# C283x_DSP.net
KiCad netlist of a schematic drawn in Altium Designer
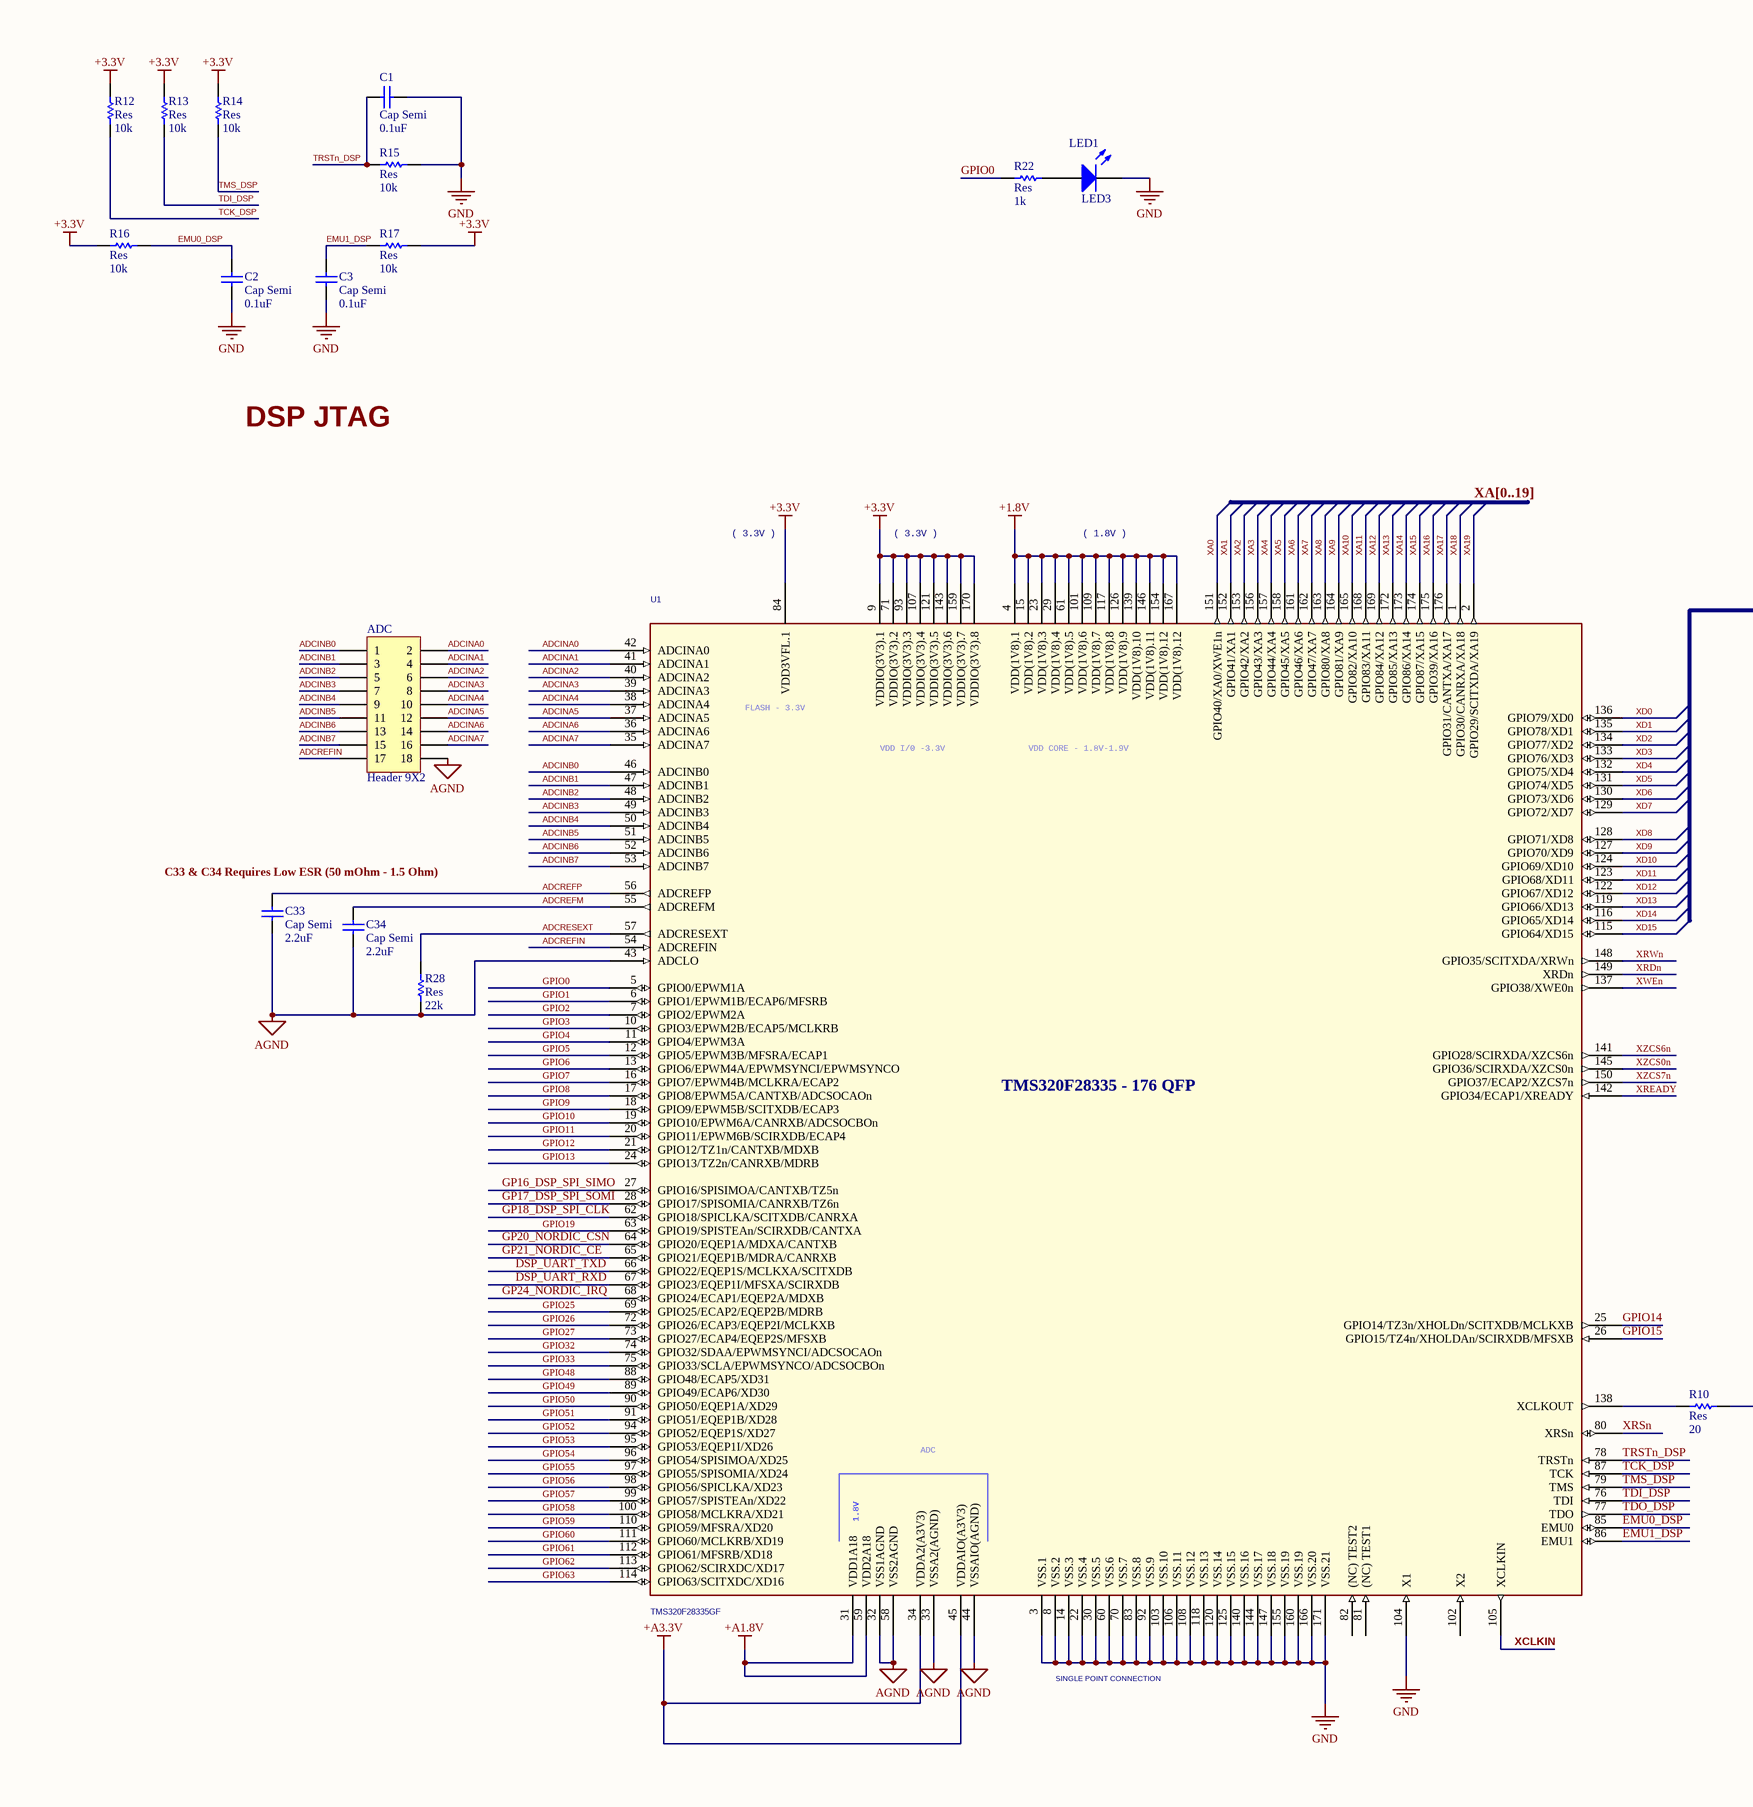
[diagram p0: C283x_DSP.SchDoc, left]
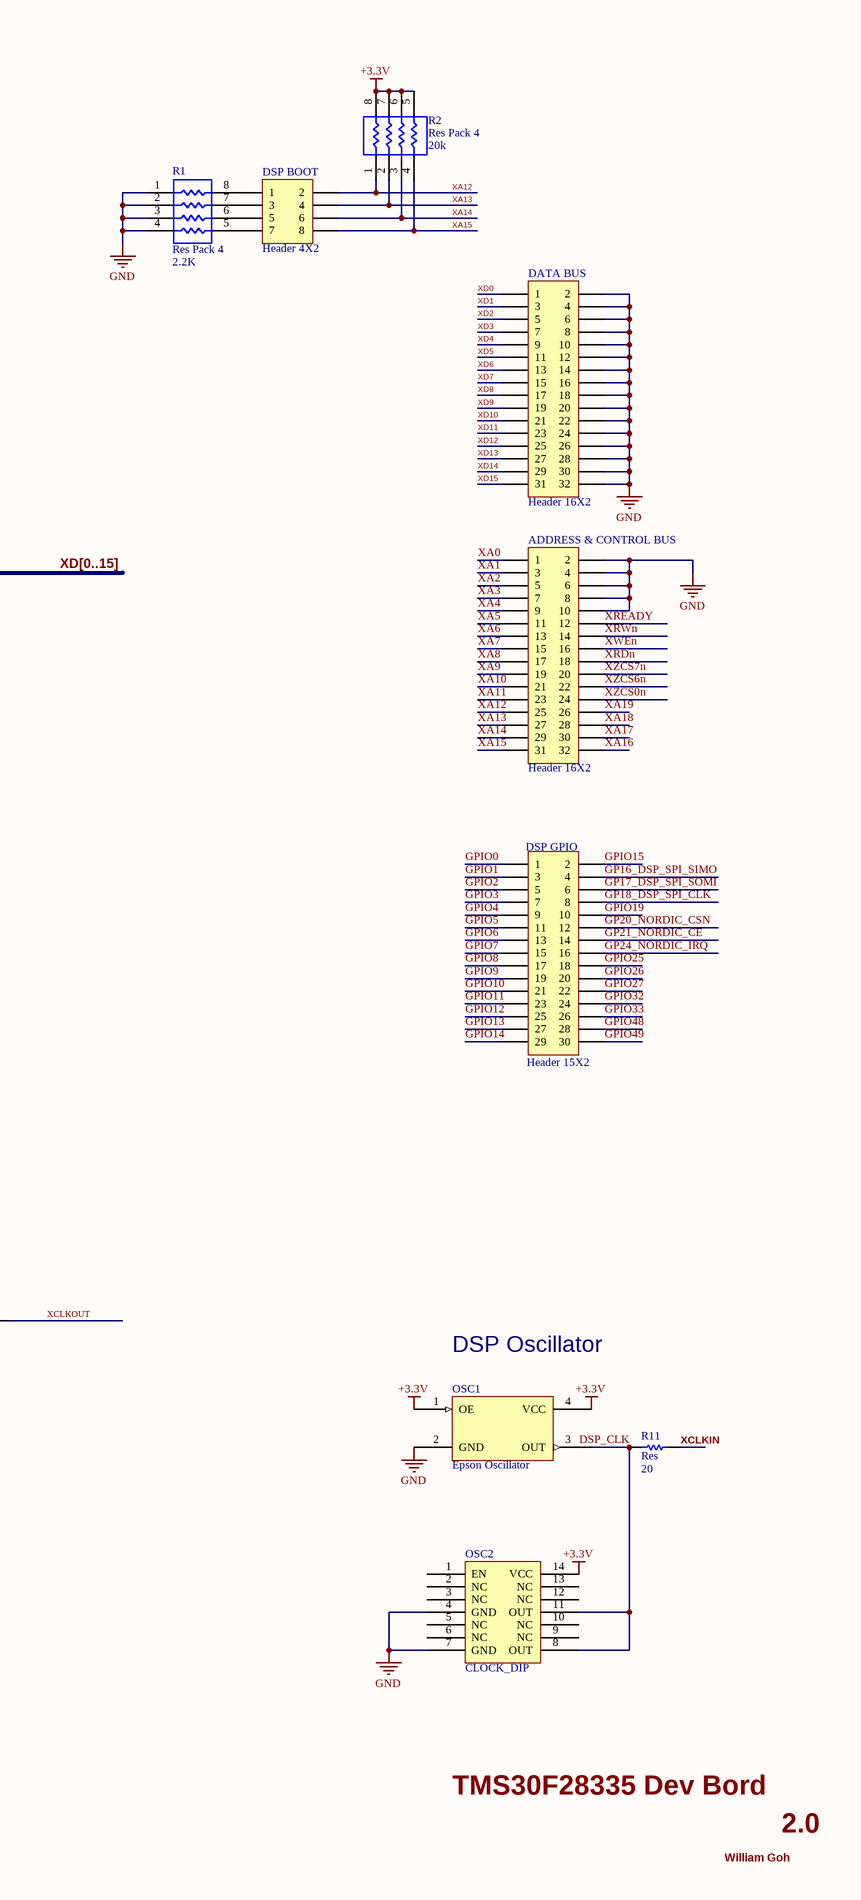
[diagram p1: C283x_DSP.SchDoc, right]

(export (version "E")
  (design (tool "Eeschema 10.0.6"))
  (components
    (comp (ref "ADC")
      (value "Header 9X2")
      (footprint "HDR2X9")
      (description "Header, 9-Pin, Dual row")
      (fields (field (name "PUBLISHER") "Altium Limited"))
      (libsource (lib "Miscellaneous Connectors") (part "Header 9X2"))
    )
    (comp (ref "ADDRESS & CONTROL BUS")
      (value "Header 16X2")
      (footprint "HDR2X16")
      (description "Header, 16-Pin, Dual row")
      (fields (field (name "PUBLISHER") "Altium Limited"))
      (libsource (lib "Miscellaneous Connectors") (part "Header 16X2"))
    )
    (comp (ref "C1")
      (value "Cap Semi")
      (footprint "0805")
      (description "Capacitor (Semiconductor SIM Model)")
      (fields (field (name "ALTIUM_VALUE") "0.1uF") (field (name "PUBLISHER") "Altium Limited"))
      (libsource (lib "Miscellaneous Devices") (part "Cap Semi"))
    )
    (comp (ref "C2")
      (value "Cap Semi")
      (footprint "0805")
      (description "Capacitor (Semiconductor SIM Model)")
      (fields (field (name "ALTIUM_VALUE") "0.1uF") (field (name "PUBLISHER") "Altium Limited"))
      (libsource (lib "Miscellaneous Devices") (part "Cap Semi"))
    )
    (comp (ref "C3")
      (value "Cap Semi")
      (footprint "0805")
      (description "Capacitor (Semiconductor SIM Model)")
      (fields (field (name "ALTIUM_VALUE") "0.1uF") (field (name "PUBLISHER") "Altium Limited"))
      (libsource (lib "Miscellaneous Devices") (part "Cap Semi"))
    )
    (comp (ref "C33")
      (value "Cap Semi")
      (footprint "0805")
      (description "Capacitor (Semiconductor SIM Model)")
      (fields (field (name "ALTIUM_VALUE") "2.2uF") (field (name "PUBLISHER") "Altium Limited"))
      (libsource (lib "Miscellaneous Devices") (part "Cap Semi"))
    )
    (comp (ref "C34")
      (value "Cap Semi")
      (footprint "0805")
      (description "Capacitor (Semiconductor SIM Model)")
      (fields (field (name "ALTIUM_VALUE") "2.2uF") (field (name "PUBLISHER") "Altium Limited"))
      (libsource (lib "Miscellaneous Devices") (part "Cap Semi"))
    )
    (comp (ref "DATA BUS")
      (value "Header 16X2")
      (footprint "HDR2X16")
      (description "Header, 16-Pin, Dual row")
      (fields (field (name "PUBLISHER") "Altium Limited"))
      (libsource (lib "Miscellaneous Connectors") (part "Header 16X2"))
    )
    (comp (ref "DSP BOOT")
      (value "Header 4X2")
      (footprint "HDR2X4")
      (description "Header, 4-Pin, Dual row")
      (fields (field (name "PUBLISHER") "Altium Limited"))
      (libsource (lib "Miscellaneous Connectors") (part "Header 4X2"))
    )
    (comp (ref "DSP GPIO")
      (value "Header 15X2")
      (footprint "HDR2X15")
      (description "Header, 15-Pin, Dual row")
      (fields (field (name "PUBLISHER") "Altium Limited"))
      (libsource (lib "Miscellaneous Connectors") (part "Header 15X2"))
    )
    (comp (ref "LED1")
      (value "LED3")
      (footprint "0805")
      (description "Typical BLUE SiC LED")
      (fields (field (name "PUBLISHER") "Altium Limited"))
      (libsource (lib "Miscellaneous Devices") (part "LED3"))
    )
    (comp (ref "OSC1")
      (value "Epson Oscillator")
      (footprint "Oscillator")
      (description "15Mhz Epson Clock")
      (libsource (lib "F28335_DSC_Breakout") (part "Oscillator"))
    )
    (comp (ref "OSC2") (value "CLOCK_DIP") (footprint "DIP-14") (libsource (lib "*") (part "CLOCK_DIP")))
    (comp (ref "R1")
      (value "Res Pack 4")
      (footprint "SO-8")
      (description "4 Isolated Resistor Network")
      (fields (field (name "ALTIUM_VALUE") "2.2K") (field (name "PUBLISHER") "Altium Limited"))
      (libsource (lib "F28335_DSC_Breakout") (part "Res Pack 4"))
    )
    (comp (ref "R2")
      (value "Res Pack 4")
      (footprint "SO-8")
      (description "4 Isolated Resistor Network")
      (fields (field (name "ALTIUM_VALUE") "20k") (field (name "PUBLISHER") "Altium Limited"))
      (libsource (lib "F28335_DSC_Breakout") (part "Res Pack 4"))
    )
    (comp (ref "R10")
      (value "Res")
      (footprint "0805")
      (description "Semiconductor Resistor")
      (fields (field (name "ALTIUM_VALUE") "20") (field (name "PUBLISHER") "Altium Limited"))
      (libsource (lib "F28335_DSC_Breakout") (part "Res Semi"))
    )
    (comp (ref "R11")
      (value "Res")
      (footprint "0805")
      (description "Semiconductor Resistor")
      (fields (field (name "ALTIUM_VALUE") "20") (field (name "PUBLISHER") "Altium Limited"))
      (libsource (lib "F28335_DSC_Breakout") (part "Res Semi"))
    )
    (comp (ref "R12")
      (value "Res")
      (footprint "0805")
      (description "Semiconductor Resistor")
      (fields (field (name "ALTIUM_VALUE") "10k") (field (name "PUBLISHER") "Altium Limited"))
      (libsource (lib "F28335_DSC_Breakout") (part "Res Semi"))
    )
    (comp (ref "R13")
      (value "Res")
      (footprint "0805")
      (description "Semiconductor Resistor")
      (fields (field (name "ALTIUM_VALUE") "10k") (field (name "PUBLISHER") "Altium Limited"))
      (libsource (lib "F28335_DSC_Breakout") (part "Res Semi"))
    )
    (comp (ref "R14")
      (value "Res")
      (footprint "0805")
      (description "Semiconductor Resistor")
      (fields (field (name "ALTIUM_VALUE") "10k") (field (name "PUBLISHER") "Altium Limited"))
      (libsource (lib "F28335_DSC_Breakout") (part "Res Semi"))
    )
    (comp (ref "R15")
      (value "Res")
      (footprint "0805")
      (description "Semiconductor Resistor")
      (fields (field (name "ALTIUM_VALUE") "10k") (field (name "PUBLISHER") "Altium Limited"))
      (libsource (lib "F28335_DSC_Breakout") (part "Res Semi"))
    )
    (comp (ref "R16")
      (value "Res")
      (footprint "0805")
      (description "Semiconductor Resistor")
      (fields (field (name "ALTIUM_VALUE") "10k") (field (name "PUBLISHER") "Altium Limited"))
      (libsource (lib "F28335_DSC_Breakout") (part "Res Semi"))
    )
    (comp (ref "R17")
      (value "Res")
      (footprint "0805")
      (description "Semiconductor Resistor")
      (fields (field (name "ALTIUM_VALUE") "10k") (field (name "PUBLISHER") "Altium Limited"))
      (libsource (lib "F28335_DSC_Breakout") (part "Res Semi"))
    )
    (comp (ref "R22")
      (value "Res")
      (footprint "0805")
      (description "Semiconductor Resistor")
      (fields (field (name "ALTIUM_VALUE") "1k") (field (name "PUBLISHER") "Altium Limited"))
      (libsource (lib "F28335_DSC_Breakout") (part "Res Semi"))
    )
    (comp (ref "R28")
      (value "Res")
      (footprint "0805")
      (description "Semiconductor Resistor")
      (fields (field (name "ALTIUM_VALUE") "22k") (field (name "PUBLISHER") "Altium Limited"))
      (libsource (lib "F28335_DSC_Breakout") (part "Res Semi"))
    )
    (comp (ref "U1")
      (value "TMS320F28335GF")
      (footprint "QFP176")
      (description "Texas Instruments F28335")
      (libsource (lib "addl") (part "TMS320F283XXPGF_23"))
    )
  )
  (nets
    (net (code "1") (name "+1.8V") (class "Default")
      (node (ref "U1") (pin "101") (pinfunction "VDD(1V8).6_101") (pintype "power_in"))
      (node (ref "U1") (pin "109") (pinfunction "VDD(1V8).7_109") (pintype "power_in"))
      (node (ref "U1") (pin "117") (pinfunction "VDD(1V8).8_117") (pintype "power_in"))
      (node (ref "U1") (pin "126") (pinfunction "VDD(1V8).9_126") (pintype "power_in"))
      (node (ref "U1") (pin "139") (pinfunction "VDD(1V8).10_139") (pintype "power_in"))
      (node (ref "U1") (pin "146") (pinfunction "VDD(1V8).11_146") (pintype "power_in"))
      (node (ref "U1") (pin "15") (pinfunction "VDD(1V8).2_15") (pintype "power_in"))
      (node (ref "U1") (pin "154") (pinfunction "VDD(1V8).12_154") (pintype "power_in"))
      (node (ref "U1") (pin "167") (pinfunction "VDD(1V8).12_167") (pintype "power_in"))
      (node (ref "U1") (pin "23") (pinfunction "VDD(1V8).3_23") (pintype "power_in"))
      (node (ref "U1") (pin "29") (pinfunction "VDD(1V8).4_29") (pintype "power_in"))
      (node (ref "U1") (pin "4") (pinfunction "VDD(1V8).1_4") (pintype "power_in"))
      (node (ref "U1") (pin "61") (pinfunction "VDD(1V8).5_61") (pintype "power_in"))
    )
    (net (code "2") (name "+3.3V") (class "Default")
      (node (ref "OSC1") (pin "1") (pinfunction "OE_1") (pintype "input"))
      (node (ref "OSC1") (pin "4") (pinfunction "VCC_4") (pintype "power_in"))
      (node (ref "OSC2") (pin "14") (pinfunction "VCC_14") (pintype "passive"))
      (node (ref "R12") (pin "2") (pinfunction "2_2") (pintype "passive"))
      (node (ref "R13") (pin "2") (pinfunction "2_2") (pintype "passive"))
      (node (ref "R14") (pin "2") (pinfunction "2_2") (pintype "passive"))
      (node (ref "R16") (pin "1") (pinfunction "1_1") (pintype "passive"))
      (node (ref "R17") (pin "2") (pinfunction "2_2") (pintype "passive"))
      (node (ref "R2") (pin "5") (pinfunction "5_5") (pintype "passive"))
      (node (ref "R2") (pin "6") (pinfunction "6_6") (pintype "passive"))
      (node (ref "R2") (pin "7") (pinfunction "7_7") (pintype "passive"))
      (node (ref "R2") (pin "8") (pinfunction "8_8") (pintype "passive"))
      (node (ref "U1") (pin "107") (pinfunction "VDDIO(3V3).4_107") (pintype "power_in"))
      (node (ref "U1") (pin "121") (pinfunction "VDDIO(3V3).5_121") (pintype "power_in"))
      (node (ref "U1") (pin "143") (pinfunction "VDDIO(3V3).6_143") (pintype "power_in"))
      (node (ref "U1") (pin "159") (pinfunction "VDDIO(3V3).7_159") (pintype "power_in"))
      (node (ref "U1") (pin "170") (pinfunction "VDDIO(3V3).8_170") (pintype "power_in"))
      (node (ref "U1") (pin "71") (pinfunction "VDDIO(3V3).2_71") (pintype "power_in"))
      (node (ref "U1") (pin "84") (pinfunction "VDD3VFL.1_84") (pintype "power_in"))
      (node (ref "U1") (pin "9") (pinfunction "VDDIO(3V3).1_9") (pintype "power_in"))
      (node (ref "U1") (pin "93") (pinfunction "VDDIO(3V3).3_93") (pintype "power_in"))
    )
    (net (code "3") (name "+A1.8V") (class "Default")
      (node (ref "U1") (pin "31") (pinfunction "VDD1A18_31") (pintype "power_in"))
      (node (ref "U1") (pin "59") (pinfunction "VDD2A18_59") (pintype "power_in"))
    )
    (net (code "4") (name "+A3.3V") (class "Default")
      (node (ref "U1") (pin "34") (pinfunction "VDDA2(A3V3)_34") (pintype "power_in"))
      (node (ref "U1") (pin "45") (pinfunction "VDDAIO(A3V3)_45") (pintype "power_in"))
    )
    (net (code "5") (name "/ADCINA0") (class "Default")
      (node (ref "ADC") (pin "2") (pinfunction "2_2") (pintype "passive"))
      (node (ref "U1") (pin "42") (pinfunction "ADCINA0_42") (pintype "input"))
    )
    (net (code "6") (name "/ADCINA1") (class "Default")
      (node (ref "ADC") (pin "4") (pinfunction "4_4") (pintype "passive"))
      (node (ref "U1") (pin "41") (pinfunction "ADCINA1_41") (pintype "input"))
    )
    (net (code "7") (name "/ADCINA2") (class "Default")
      (node (ref "ADC") (pin "6") (pinfunction "6_6") (pintype "passive"))
      (node (ref "U1") (pin "40") (pinfunction "ADCINA2_40") (pintype "input"))
    )
    (net (code "8") (name "/ADCINA3") (class "Default")
      (node (ref "ADC") (pin "8") (pinfunction "8_8") (pintype "passive"))
      (node (ref "U1") (pin "39") (pinfunction "ADCINA3_39") (pintype "input"))
    )
    (net (code "9") (name "/ADCINA4") (class "Default")
      (node (ref "ADC") (pin "10") (pinfunction "10_10") (pintype "passive"))
      (node (ref "U1") (pin "38") (pinfunction "ADCINA4_38") (pintype "input"))
    )
    (net (code "10") (name "/ADCINA5") (class "Default")
      (node (ref "ADC") (pin "12") (pinfunction "12_12") (pintype "passive"))
      (node (ref "U1") (pin "37") (pinfunction "ADCINA5_37") (pintype "input"))
    )
    (net (code "11") (name "/ADCINA6") (class "Default")
      (node (ref "ADC") (pin "14") (pinfunction "14_14") (pintype "passive"))
      (node (ref "U1") (pin "36") (pinfunction "ADCINA6_36") (pintype "input"))
    )
    (net (code "12") (name "/ADCINA7") (class "Default")
      (node (ref "ADC") (pin "16") (pinfunction "16_16") (pintype "passive"))
      (node (ref "U1") (pin "35") (pinfunction "ADCINA7_35") (pintype "input"))
    )
    (net (code "13") (name "/ADCINB0") (class "Default")
      (node (ref "ADC") (pin "1") (pinfunction "1_1") (pintype "passive"))
      (node (ref "U1") (pin "46") (pinfunction "ADCINB0_46") (pintype "input"))
    )
    (net (code "14") (name "/ADCINB1") (class "Default")
      (node (ref "ADC") (pin "3") (pinfunction "3_3") (pintype "passive"))
      (node (ref "U1") (pin "47") (pinfunction "ADCINB1_47") (pintype "input"))
    )
    (net (code "15") (name "/ADCINB2") (class "Default")
      (node (ref "ADC") (pin "5") (pinfunction "5_5") (pintype "passive"))
      (node (ref "U1") (pin "48") (pinfunction "ADCINB2_48") (pintype "input"))
    )
    (net (code "16") (name "/ADCINB3") (class "Default")
      (node (ref "ADC") (pin "7") (pinfunction "7_7") (pintype "passive"))
      (node (ref "U1") (pin "49") (pinfunction "ADCINB3_49") (pintype "input"))
    )
    (net (code "17") (name "/ADCINB4") (class "Default")
      (node (ref "ADC") (pin "9") (pinfunction "9_9") (pintype "passive"))
      (node (ref "U1") (pin "50") (pinfunction "ADCINB4_50") (pintype "input"))
    )
    (net (code "18") (name "/ADCINB5") (class "Default")
      (node (ref "ADC") (pin "11") (pinfunction "11_11") (pintype "passive"))
      (node (ref "U1") (pin "51") (pinfunction "ADCINB5_51") (pintype "input"))
    )
    (net (code "19") (name "/ADCINB6") (class "Default")
      (node (ref "ADC") (pin "13") (pinfunction "13_13") (pintype "passive"))
      (node (ref "U1") (pin "52") (pinfunction "ADCINB6_52") (pintype "input"))
    )
    (net (code "20") (name "/ADCINB7") (class "Default")
      (node (ref "ADC") (pin "15") (pinfunction "15_15") (pintype "passive"))
      (node (ref "U1") (pin "53") (pinfunction "ADCINB7_53") (pintype "input"))
    )
    (net (code "21") (name "/ADCREFIN") (class "Default")
      (node (ref "ADC") (pin "17") (pinfunction "17_17") (pintype "passive"))
      (node (ref "U1") (pin "54") (pinfunction "ADCREFIN_54") (pintype "input"))
    )
    (net (code "22") (name "/ADCREFM") (class "Default")
      (node (ref "C34") (pin "1") (pinfunction "1_1") (pintype "passive"))
      (node (ref "U1") (pin "55") (pinfunction "ADCREFM_55") (pintype "output"))
    )
    (net (code "23") (name "/ADCREFP") (class "Default")
      (node (ref "C33") (pin "1") (pinfunction "1_1") (pintype "passive"))
      (node (ref "U1") (pin "56") (pinfunction "ADCREFP_56") (pintype "output"))
    )
    (net (code "24") (name "/ADCRESEXT") (class "Default")
      (node (ref "R28") (pin "2") (pinfunction "2_2") (pintype "passive"))
      (node (ref "U1") (pin "57") (pinfunction "ADCRESEXT_57") (pintype "output"))
    )
    (net (code "26") (name "/DSP_UART_RXD") (class "Default")
      (node (ref "U1") (pin "67") (pinfunction "GPIO23/EQEP1I/MFSXA/SCIRXDB_67") (pintype "bidirectional"))
    )
    (net (code "27") (name "/DSP_UART_TXD") (class "Default")
      (node (ref "U1") (pin "66") (pinfunction "GPIO22/EQEP1S/MCLKXA/SCITXDB_66") (pintype "bidirectional"))
    )
    (net (code "28") (name "/EMU0_DSP") (class "Default")
      (node (ref "C2") (pin "2") (pinfunction "2_2") (pintype "passive"))
      (node (ref "R16") (pin "2") (pinfunction "2_2") (pintype "passive"))
      (node (ref "U1") (pin "85") (pinfunction "EMU0_85") (pintype "bidirectional"))
    )
    (net (code "29") (name "/EMU1_DSP") (class "Default")
      (node (ref "C3") (pin "2") (pinfunction "2_2") (pintype "passive"))
      (node (ref "R17") (pin "1") (pinfunction "1_1") (pintype "passive"))
      (node (ref "U1") (pin "86") (pinfunction "EMU1_86") (pintype "bidirectional"))
    )
    (net (code "30") (name "/GP16_DSP_SPI_SIMO") (class "Default")
      (node (ref "DSP GPIO") (pin "4") (pinfunction "4_4") (pintype "passive"))
      (node (ref "U1") (pin "27") (pinfunction "GPIO16/SPISIMOA/CANTXB/TZ5n_27") (pintype "bidirectional"))
    )
    (net (code "31") (name "/GP17_DSP_SPI_SOMI") (class "Default")
      (node (ref "DSP GPIO") (pin "6") (pinfunction "6_6") (pintype "passive"))
      (node (ref "U1") (pin "28") (pinfunction "GPIO17/SPISOMIA/CANRXB/TZ6n_28") (pintype "bidirectional"))
    )
    (net (code "32") (name "/GP18_DSP_SPI_CLK") (class "Default")
      (node (ref "DSP GPIO") (pin "8") (pinfunction "8_8") (pintype "passive"))
      (node (ref "U1") (pin "62") (pinfunction "GPIO18/SPICLKA/SCITXDB/CANRXA_62") (pintype "bidirectional"))
    )
    (net (code "33") (name "/GP20_NORDIC_CSN") (class "Default")
      (node (ref "DSP GPIO") (pin "12") (pinfunction "12_12") (pintype "passive"))
      (node (ref "U1") (pin "64") (pinfunction "GPIO20/EQEP1A/MDXA/CANTXB_64") (pintype "bidirectional"))
    )
    (net (code "34") (name "/GP21_NORDIC_CE") (class "Default")
      (node (ref "DSP GPIO") (pin "14") (pinfunction "14_14") (pintype "passive"))
      (node (ref "U1") (pin "65") (pinfunction "GPIO21/EQEP1B/MDRA/CANRXB_65") (pintype "bidirectional"))
    )
    (net (code "35") (name "/GP24_NORDIC_IRQ") (class "Default")
      (node (ref "DSP GPIO") (pin "16") (pinfunction "16_16") (pintype "passive"))
      (node (ref "U1") (pin "68") (pinfunction "GPIO24/ECAP1/EQEP2A/MDXB_68") (pintype "bidirectional"))
    )
    (net (code "36") (name "/GPIO0") (class "Default")
      (node (ref "DSP GPIO") (pin "1") (pinfunction "1_1") (pintype "passive"))
      (node (ref "R22") (pin "1") (pinfunction "1_1") (pintype "passive"))
      (node (ref "U1") (pin "5") (pinfunction "GPIO0/EPWM1A_5") (pintype "bidirectional"))
    )
    (net (code "37") (name "/GPIO1") (class "Default")
      (node (ref "DSP GPIO") (pin "3") (pinfunction "3_3") (pintype "passive"))
      (node (ref "U1") (pin "6") (pinfunction "GPIO1/EPWM1B/ECAP6/MFSRB_6") (pintype "bidirectional"))
    )
    (net (code "38") (name "/GPIO2") (class "Default")
      (node (ref "DSP GPIO") (pin "5") (pinfunction "5_5") (pintype "passive"))
      (node (ref "U1") (pin "7") (pinfunction "GPIO2/EPWM2A_7") (pintype "bidirectional"))
    )
    (net (code "39") (name "/GPIO3") (class "Default")
      (node (ref "DSP GPIO") (pin "7") (pinfunction "7_7") (pintype "passive"))
      (node (ref "U1") (pin "10") (pinfunction "GPIO3/EPWM2B/ECAP5/MCLKRB_10") (pintype "bidirectional"))
    )
    (net (code "40") (name "/GPIO4") (class "Default")
      (node (ref "DSP GPIO") (pin "9") (pinfunction "9_9") (pintype "passive"))
      (node (ref "U1") (pin "11") (pinfunction "GPIO4/EPWM3A_11") (pintype "bidirectional"))
    )
    (net (code "41") (name "/GPIO5") (class "Default")
      (node (ref "DSP GPIO") (pin "11") (pinfunction "11_11") (pintype "passive"))
      (node (ref "U1") (pin "12") (pinfunction "GPIO5/EPWM3B/MFSRA/ECAP1_12") (pintype "bidirectional"))
    )
    (net (code "42") (name "/GPIO6") (class "Default")
      (node (ref "DSP GPIO") (pin "13") (pinfunction "13_13") (pintype "passive"))
      (node (ref "U1") (pin "13") (pinfunction "GPIO6/EPWM4A/EPWMSYNCI/EPWMSYNCO_13") (pintype "bidirectional"))
    )
    (net (code "43") (name "/GPIO7") (class "Default")
      (node (ref "DSP GPIO") (pin "15") (pinfunction "15_15") (pintype "passive"))
      (node (ref "U1") (pin "16") (pinfunction "GPIO7/EPWM4B/MCLKRA/ECAP2_16") (pintype "bidirectional"))
    )
    (net (code "44") (name "/GPIO8") (class "Default")
      (node (ref "DSP GPIO") (pin "17") (pinfunction "17_17") (pintype "passive"))
      (node (ref "U1") (pin "17") (pinfunction "GPIO8/EPWM5A/CANTXB/ADCSOCAOn_17") (pintype "bidirectional"))
    )
    (net (code "45") (name "/GPIO9") (class "Default")
      (node (ref "DSP GPIO") (pin "19") (pinfunction "19_19") (pintype "passive"))
      (node (ref "U1") (pin "18") (pinfunction "GPIO9/EPWM5B/SCITXDB/ECAP3_18") (pintype "bidirectional"))
    )
    (net (code "46") (name "/GPIO10") (class "Default")
      (node (ref "DSP GPIO") (pin "21") (pinfunction "21_21") (pintype "passive"))
      (node (ref "U1") (pin "19") (pinfunction "GPIO10/EPWM6A/CANRXB/ADCSOCBOn_19") (pintype "bidirectional"))
    )
    (net (code "47") (name "/GPIO11") (class "Default")
      (node (ref "DSP GPIO") (pin "23") (pinfunction "23_23") (pintype "passive"))
      (node (ref "U1") (pin "20") (pinfunction "GPIO11/EPWM6B/SCIRXDB/ECAP4_20") (pintype "bidirectional"))
    )
    (net (code "48") (name "/GPIO12") (class "Default")
      (node (ref "DSP GPIO") (pin "25") (pinfunction "25_25") (pintype "passive"))
      (node (ref "U1") (pin "21") (pinfunction "GPIO12/TZ1n/CANTXB/MDXB_21") (pintype "bidirectional"))
    )
    (net (code "49") (name "/GPIO13") (class "Default")
      (node (ref "DSP GPIO") (pin "27") (pinfunction "27_27") (pintype "passive"))
      (node (ref "U1") (pin "24") (pinfunction "GPIO13/TZ2n/CANRXB/MDRB_24") (pintype "bidirectional"))
    )
    (net (code "50") (name "/GPIO14") (class "Default")
      (node (ref "DSP GPIO") (pin "29") (pinfunction "29_29") (pintype "passive"))
      (node (ref "U1") (pin "25") (pinfunction "GPIO14/TZ3n/XHOLDn/SCITXDB/MCLKXB_25") (pintype "output"))
    )
    (net (code "51") (name "/GPIO15") (class "Default")
      (node (ref "DSP GPIO") (pin "2") (pinfunction "2_2") (pintype "passive"))
      (node (ref "U1") (pin "26") (pinfunction "GPIO15/TZ4n/XHOLDAn/SCIRXDB/MFSXB_26") (pintype "input"))
    )
    (net (code "52") (name "/GPIO19") (class "Default")
      (node (ref "DSP GPIO") (pin "10") (pinfunction "10_10") (pintype "passive"))
      (node (ref "U1") (pin "63") (pinfunction "GPIO19/SPISTEAn/SCIRXDB/CANTXA_63") (pintype "bidirectional"))
    )
    (net (code "53") (name "/GPIO25") (class "Default")
      (node (ref "DSP GPIO") (pin "18") (pinfunction "18_18") (pintype "passive"))
      (node (ref "U1") (pin "69") (pinfunction "GPIO25/ECAP2/EQEP2B/MDRB_69") (pintype "bidirectional"))
    )
    (net (code "54") (name "/GPIO26") (class "Default")
      (node (ref "DSP GPIO") (pin "20") (pinfunction "20_20") (pintype "passive"))
      (node (ref "U1") (pin "72") (pinfunction "GPIO26/ECAP3/EQEP2I/MCLKXB_72") (pintype "bidirectional"))
    )
    (net (code "55") (name "/GPIO27") (class "Default")
      (node (ref "DSP GPIO") (pin "22") (pinfunction "22_22") (pintype "passive"))
      (node (ref "U1") (pin "73") (pinfunction "GPIO27/ECAP4/EQEP2S/MFSXB_73") (pintype "bidirectional"))
    )
    (net (code "56") (name "/GPIO32") (class "Default")
      (node (ref "DSP GPIO") (pin "24") (pinfunction "24_24") (pintype "passive"))
      (node (ref "U1") (pin "74") (pinfunction "GPIO32/SDAA/EPWMSYNCI/ADCSOCAOn_74") (pintype "bidirectional"))
    )
    (net (code "57") (name "/GPIO33") (class "Default")
      (node (ref "DSP GPIO") (pin "26") (pinfunction "26_26") (pintype "passive"))
      (node (ref "U1") (pin "75") (pinfunction "GPIO33/SCLA/EPWMSYNCO/ADCSOCBOn_75") (pintype "bidirectional"))
    )
    (net (code "58") (name "/GPIO48") (class "Default")
      (node (ref "DSP GPIO") (pin "28") (pinfunction "28_28") (pintype "passive"))
      (node (ref "U1") (pin "88") (pinfunction "GPIO48/ECAP5/XD31_88") (pintype "bidirectional"))
    )
    (net (code "59") (name "/GPIO49") (class "Default")
      (node (ref "DSP GPIO") (pin "30") (pinfunction "30_30") (pintype "passive"))
      (node (ref "U1") (pin "89") (pinfunction "GPIO49/ECAP6/XD30_89") (pintype "bidirectional"))
    )
    (net (code "60") (name "/GPIO50") (class "Default")
      (node (ref "U1") (pin "90") (pinfunction "GPIO50/EQEP1A/XD29_90") (pintype "bidirectional"))
    )
    (net (code "61") (name "/GPIO51") (class "Default")
      (node (ref "U1") (pin "91") (pinfunction "GPIO51/EQEP1B/XD28_91") (pintype "bidirectional"))
    )
    (net (code "62") (name "/GPIO52") (class "Default")
      (node (ref "U1") (pin "94") (pinfunction "GPIO52/EQEP1S/XD27_94") (pintype "bidirectional"))
    )
    (net (code "63") (name "/GPIO53") (class "Default")
      (node (ref "U1") (pin "95") (pinfunction "GPIO53/EQEP1I/XD26_95") (pintype "bidirectional"))
    )
    (net (code "64") (name "/GPIO54") (class "Default")
      (node (ref "U1") (pin "96") (pinfunction "GPIO54/SPISIMOA/XD25_96") (pintype "bidirectional"))
    )
    (net (code "65") (name "/GPIO55") (class "Default")
      (node (ref "U1") (pin "97") (pinfunction "GPIO55/SPISOMIA/XD24_97") (pintype "bidirectional"))
    )
    (net (code "66") (name "/GPIO56") (class "Default")
      (node (ref "U1") (pin "98") (pinfunction "GPIO56/SPICLKA/XD23_98") (pintype "bidirectional"))
    )
    (net (code "67") (name "/GPIO57") (class "Default")
      (node (ref "U1") (pin "99") (pinfunction "GPIO57/SPISTEAn/XD22_99") (pintype "bidirectional"))
    )
    (net (code "68") (name "/GPIO58") (class "Default")
      (node (ref "U1") (pin "100") (pinfunction "GPIO58/MCLKRA/XD21_100") (pintype "bidirectional"))
    )
    (net (code "69") (name "/GPIO59") (class "Default")
      (node (ref "U1") (pin "110") (pinfunction "GPIO59/MFSRA/XD20_110") (pintype "bidirectional"))
    )
    (net (code "70") (name "/GPIO60") (class "Default")
      (node (ref "U1") (pin "111") (pinfunction "GPIO60/MCLKRB/XD19_111") (pintype "bidirectional"))
    )
    (net (code "71") (name "/GPIO61") (class "Default")
      (node (ref "U1") (pin "112") (pinfunction "GPIO61/MFSRB/XD18_112") (pintype "bidirectional"))
    )
    (net (code "72") (name "/GPIO62") (class "Default")
      (node (ref "U1") (pin "113") (pinfunction "GPIO62/SCIRXDC/XD17_113") (pintype "bidirectional"))
    )
    (net (code "73") (name "/GPIO63") (class "Default")
      (node (ref "U1") (pin "114") (pinfunction "GPIO63/SCITXDC/XD16_114") (pintype "bidirectional"))
    )
    (net (code "74") (name "/TCK_DSP") (class "Default")
      (node (ref "R12") (pin "1") (pinfunction "1_1") (pintype "passive"))
      (node (ref "U1") (pin "87") (pinfunction "TCK_87") (pintype "input"))
    )
    (net (code "75") (name "/TDI_DSP") (class "Default")
      (node (ref "R13") (pin "1") (pinfunction "1_1") (pintype "passive"))
      (node (ref "U1") (pin "76") (pinfunction "TDI_76") (pintype "input"))
    )
    (net (code "76") (name "/TDO_DSP") (class "Default")
      (node (ref "U1") (pin "77") (pinfunction "TDO_77") (pintype "output"))
    )
    (net (code "77") (name "/TMS_DSP") (class "Default")
      (node (ref "R14") (pin "1") (pinfunction "1_1") (pintype "passive"))
      (node (ref "U1") (pin "79") (pinfunction "TMS_79") (pintype "input"))
    )
    (net (code "78") (name "/TRSTn_DSP") (class "Default")
      (node (ref "C1") (pin "2") (pinfunction "2_2") (pintype "passive"))
      (node (ref "R15") (pin "1") (pinfunction "1_1") (pintype "passive"))
      (node (ref "U1") (pin "78") (pinfunction "TRSTn_78") (pintype "input"))
    )
    (net (code "79") (name "/XA0") (class "Default")
      (node (ref "ADDRESS & CONTROL BUS") (pin "1") (pinfunction "1_1") (pintype "passive"))
      (node (ref "U1") (pin "151") (pinfunction "GPIO40/XA0/XWE1n_151") (pintype "output"))
    )
    (net (code "80") (name "/XA1") (class "Default")
      (node (ref "ADDRESS & CONTROL BUS") (pin "3") (pinfunction "3_3") (pintype "passive"))
      (node (ref "U1") (pin "152") (pinfunction "GPIO41/XA1_152") (pintype "output"))
    )
    (net (code "81") (name "/XA2") (class "Default")
      (node (ref "ADDRESS & CONTROL BUS") (pin "5") (pinfunction "5_5") (pintype "passive"))
      (node (ref "U1") (pin "153") (pinfunction "GPIO42/XA2_153") (pintype "output"))
    )
    (net (code "82") (name "/XA3") (class "Default")
      (node (ref "ADDRESS & CONTROL BUS") (pin "7") (pinfunction "7_7") (pintype "passive"))
      (node (ref "U1") (pin "156") (pinfunction "GPIO43/XA3_156") (pintype "output"))
    )
    (net (code "83") (name "/XA4") (class "Default")
      (node (ref "ADDRESS & CONTROL BUS") (pin "9") (pinfunction "9_9") (pintype "passive"))
      (node (ref "U1") (pin "157") (pinfunction "GPIO44/XA4_157") (pintype "output"))
    )
    (net (code "84") (name "/XA5") (class "Default")
      (node (ref "ADDRESS & CONTROL BUS") (pin "11") (pinfunction "11_11") (pintype "passive"))
      (node (ref "U1") (pin "158") (pinfunction "GPIO45/XA5_158") (pintype "output"))
    )
    (net (code "85") (name "/XA6") (class "Default")
      (node (ref "ADDRESS & CONTROL BUS") (pin "13") (pinfunction "13_13") (pintype "passive"))
      (node (ref "U1") (pin "161") (pinfunction "GPIO46/XA6_161") (pintype "output"))
    )
    (net (code "86") (name "/XA7") (class "Default")
      (node (ref "ADDRESS & CONTROL BUS") (pin "15") (pinfunction "15_15") (pintype "passive"))
      (node (ref "U1") (pin "162") (pinfunction "GPIO47/XA7_162") (pintype "output"))
    )
    (net (code "87") (name "/XA8") (class "Default")
      (node (ref "ADDRESS & CONTROL BUS") (pin "17") (pinfunction "17_17") (pintype "passive"))
      (node (ref "U1") (pin "163") (pinfunction "GPIO80/XA8_163") (pintype "output"))
    )
    (net (code "88") (name "/XA9") (class "Default")
      (node (ref "ADDRESS & CONTROL BUS") (pin "19") (pinfunction "19_19") (pintype "passive"))
      (node (ref "U1") (pin "164") (pinfunction "GPIO81/XA9_164") (pintype "output"))
    )
    (net (code "89") (name "/XA10") (class "Default")
      (node (ref "ADDRESS & CONTROL BUS") (pin "21") (pinfunction "21_21") (pintype "passive"))
      (node (ref "U1") (pin "165") (pinfunction "GPIO82/XA10_165") (pintype "output"))
    )
    (net (code "90") (name "/XA11") (class "Default")
      (node (ref "ADDRESS & CONTROL BUS") (pin "23") (pinfunction "23_23") (pintype "passive"))
      (node (ref "U1") (pin "168") (pinfunction "GPIO83/XA11_168") (pintype "output"))
    )
    (net (code "91") (name "/XA12") (class "Default")
      (node (ref "ADDRESS & CONTROL BUS") (pin "25") (pinfunction "25_25") (pintype "passive"))
      (node (ref "DSP BOOT") (pin "2") (pinfunction "2_2") (pintype "passive"))
      (node (ref "R2") (pin "1") (pinfunction "1_1") (pintype "passive"))
      (node (ref "U1") (pin "169") (pinfunction "GPIO84/XA12_169") (pintype "output"))
    )
    (net (code "92") (name "/XA13") (class "Default")
      (node (ref "ADDRESS & CONTROL BUS") (pin "27") (pinfunction "27_27") (pintype "passive"))
      (node (ref "DSP BOOT") (pin "4") (pinfunction "4_4") (pintype "passive"))
      (node (ref "R2") (pin "2") (pinfunction "2_2") (pintype "passive"))
      (node (ref "U1") (pin "172") (pinfunction "GPIO85/XA13_172") (pintype "output"))
    )
    (net (code "93") (name "/XA14") (class "Default")
      (node (ref "ADDRESS & CONTROL BUS") (pin "29") (pinfunction "29_29") (pintype "passive"))
      (node (ref "DSP BOOT") (pin "6") (pinfunction "6_6") (pintype "passive"))
      (node (ref "R2") (pin "3") (pinfunction "3_3") (pintype "passive"))
      (node (ref "U1") (pin "173") (pinfunction "GPIO86/XA14_173") (pintype "output"))
    )
    (net (code "94") (name "/XA15") (class "Default")
      (node (ref "ADDRESS & CONTROL BUS") (pin "31") (pinfunction "31_31") (pintype "passive"))
      (node (ref "DSP BOOT") (pin "8") (pinfunction "8_8") (pintype "passive"))
      (node (ref "R2") (pin "4") (pinfunction "4_4") (pintype "passive"))
      (node (ref "U1") (pin "174") (pinfunction "GPIO87/XA15_174") (pintype "output"))
    )
    (net (code "95") (name "/XA16") (class "Default")
      (node (ref "ADDRESS & CONTROL BUS") (pin "32") (pinfunction "32_32") (pintype "passive"))
      (node (ref "U1") (pin "175") (pinfunction "GPIO39/XA16_175") (pintype "output"))
    )
    (net (code "96") (name "/XA17") (class "Default")
      (node (ref "ADDRESS & CONTROL BUS") (pin "30") (pinfunction "30_30") (pintype "passive"))
      (node (ref "U1") (pin "176") (pinfunction "GPIO31/CANTXA/XA17_176") (pintype "output"))
    )
    (net (code "97") (name "/XA18") (class "Default")
      (node (ref "ADDRESS & CONTROL BUS") (pin "28") (pinfunction "28_28") (pintype "passive"))
      (node (ref "U1") (pin "1") (pinfunction "GPIO30/CANRXA/XA18_1") (pintype "output"))
    )
    (net (code "98") (name "/XA19") (class "Default")
      (node (ref "ADDRESS & CONTROL BUS") (pin "26") (pinfunction "26_26") (pintype "passive"))
      (node (ref "U1") (pin "2") (pinfunction "GPIO29/SCITXDA/XA19_2") (pintype "output"))
    )
    (net (code "100") (name "/XCLKIN") (class "Default")
      (node (ref "R11") (pin "2") (pinfunction "2_2") (pintype "passive"))
      (node (ref "U1") (pin "105") (pinfunction "XCLKIN_105") (pintype "output"))
    )
    (net (code "101") (name "/XCLKOUT") (class "Default")
      (node (ref "R10") (pin "2") (pinfunction "2_2") (pintype "passive"))
    )
    (net (code "102") (name "/XD0") (class "Default")
      (node (ref "DATA BUS") (pin "1") (pinfunction "1_1") (pintype "passive"))
      (node (ref "U1") (pin "136") (pinfunction "GPIO79/XD0_136") (pintype "bidirectional"))
    )
    (net (code "103") (name "/XD1") (class "Default")
      (node (ref "DATA BUS") (pin "3") (pinfunction "3_3") (pintype "passive"))
      (node (ref "U1") (pin "135") (pinfunction "GPIO78/XD1_135") (pintype "bidirectional"))
    )
    (net (code "104") (name "/XD2") (class "Default")
      (node (ref "DATA BUS") (pin "5") (pinfunction "5_5") (pintype "passive"))
      (node (ref "U1") (pin "134") (pinfunction "GPIO77/XD2_134") (pintype "bidirectional"))
    )
    (net (code "105") (name "/XD3") (class "Default")
      (node (ref "DATA BUS") (pin "7") (pinfunction "7_7") (pintype "passive"))
      (node (ref "U1") (pin "133") (pinfunction "GPIO76/XD3_133") (pintype "bidirectional"))
    )
    (net (code "106") (name "/XD4") (class "Default")
      (node (ref "DATA BUS") (pin "9") (pinfunction "9_9") (pintype "passive"))
      (node (ref "U1") (pin "132") (pinfunction "GPIO75/XD4_132") (pintype "bidirectional"))
    )
    (net (code "107") (name "/XD5") (class "Default")
      (node (ref "DATA BUS") (pin "11") (pinfunction "11_11") (pintype "passive"))
      (node (ref "U1") (pin "131") (pinfunction "GPIO74/XD5_131") (pintype "bidirectional"))
    )
    (net (code "108") (name "/XD6") (class "Default")
      (node (ref "DATA BUS") (pin "13") (pinfunction "13_13") (pintype "passive"))
      (node (ref "U1") (pin "130") (pinfunction "GPIO73/XD6_130") (pintype "bidirectional"))
    )
    (net (code "109") (name "/XD7") (class "Default")
      (node (ref "DATA BUS") (pin "15") (pinfunction "15_15") (pintype "passive"))
      (node (ref "U1") (pin "129") (pinfunction "GPIO72/XD7_129") (pintype "bidirectional"))
    )
    (net (code "110") (name "/XD8") (class "Default")
      (node (ref "DATA BUS") (pin "17") (pinfunction "17_17") (pintype "passive"))
      (node (ref "U1") (pin "128") (pinfunction "GPIO71/XD8_128") (pintype "bidirectional"))
    )
    (net (code "111") (name "/XD9") (class "Default")
      (node (ref "DATA BUS") (pin "19") (pinfunction "19_19") (pintype "passive"))
      (node (ref "U1") (pin "127") (pinfunction "GPIO70/XD9_127") (pintype "bidirectional"))
    )
    (net (code "112") (name "/XD10") (class "Default")
      (node (ref "DATA BUS") (pin "21") (pinfunction "21_21") (pintype "passive"))
      (node (ref "U1") (pin "124") (pinfunction "GPIO69/XD10_124") (pintype "bidirectional"))
    )
    (net (code "113") (name "/XD11") (class "Default")
      (node (ref "DATA BUS") (pin "23") (pinfunction "23_23") (pintype "passive"))
      (node (ref "U1") (pin "123") (pinfunction "GPIO68/XD11_123") (pintype "bidirectional"))
    )
    (net (code "114") (name "/XD12") (class "Default")
      (node (ref "DATA BUS") (pin "25") (pinfunction "25_25") (pintype "passive"))
      (node (ref "U1") (pin "122") (pinfunction "GPIO67/XD12_122") (pintype "bidirectional"))
    )
    (net (code "115") (name "/XD13") (class "Default")
      (node (ref "DATA BUS") (pin "27") (pinfunction "27_27") (pintype "passive"))
      (node (ref "U1") (pin "119") (pinfunction "GPIO66/XD13_119") (pintype "bidirectional"))
    )
    (net (code "116") (name "/XD14") (class "Default")
      (node (ref "DATA BUS") (pin "29") (pinfunction "29_29") (pintype "passive"))
      (node (ref "U1") (pin "116") (pinfunction "GPIO65/XD14_116") (pintype "bidirectional"))
    )
    (net (code "117") (name "/XD15") (class "Default")
      (node (ref "DATA BUS") (pin "31") (pinfunction "31_31") (pintype "passive"))
      (node (ref "U1") (pin "115") (pinfunction "GPIO64/XD15_115") (pintype "bidirectional"))
    )
    (net (code "119") (name "/XRDn") (class "Default")
      (node (ref "ADDRESS & CONTROL BUS") (pin "18") (pinfunction "18_18") (pintype "passive"))
      (node (ref "U1") (pin "149") (pinfunction "XRDn_149") (pintype "output"))
    )
    (net (code "120") (name "/XREADY") (class "Default")
      (node (ref "ADDRESS & CONTROL BUS") (pin "12") (pinfunction "12_12") (pintype "passive"))
      (node (ref "U1") (pin "142") (pinfunction "GPIO34/ECAP1/XREADY_142") (pintype "input"))
    )
    (net (code "121") (name "/XRSn") (class "Default")
      (node (ref "U1") (pin "80") (pinfunction "XRSn_80") (pintype "bidirectional"))
    )
    (net (code "122") (name "/XRWn") (class "Default")
      (node (ref "ADDRESS & CONTROL BUS") (pin "14") (pinfunction "14_14") (pintype "passive"))
      (node (ref "U1") (pin "148") (pinfunction "GPIO35/SCITXDA/XRWn_148") (pintype "output"))
    )
    (net (code "123") (name "/XWEn") (class "Default")
      (node (ref "ADDRESS & CONTROL BUS") (pin "16") (pinfunction "16_16") (pintype "passive"))
      (node (ref "U1") (pin "137") (pinfunction "GPIO38/XWE0n_137") (pintype "output"))
    )
    (net (code "124") (name "/XZCS0n") (class "Default")
      (node (ref "ADDRESS & CONTROL BUS") (pin "24") (pinfunction "24_24") (pintype "passive"))
      (node (ref "U1") (pin "145") (pinfunction "GPIO36/SCIRXDA/XZCS0n_145") (pintype "output"))
    )
    (net (code "125") (name "/XZCS6n") (class "Default")
      (node (ref "ADDRESS & CONTROL BUS") (pin "22") (pinfunction "22_22") (pintype "passive"))
      (node (ref "U1") (pin "141") (pinfunction "GPIO28/SCIRXDA/XZCS6n_141") (pintype "output"))
    )
    (net (code "126") (name "/XZCS7n") (class "Default")
      (node (ref "ADDRESS & CONTROL BUS") (pin "20") (pinfunction "20_20") (pintype "passive"))
      (node (ref "U1") (pin "150") (pinfunction "GPIO37/ECAP2/XZCS7n_150") (pintype "output"))
    )
    (net (code "127") (name "AGND") (class "Default")
      (node (ref "ADC") (pin "18") (pinfunction "18_18") (pintype "passive"))
      (node (ref "C33") (pin "2") (pinfunction "2_2") (pintype "passive"))
      (node (ref "C34") (pin "2") (pinfunction "2_2") (pintype "passive"))
      (node (ref "R28") (pin "1") (pinfunction "1_1") (pintype "passive"))
      (node (ref "U1") (pin "32") (pinfunction "VSS1AGND_32") (pintype "power_in"))
      (node (ref "U1") (pin "33") (pinfunction "VSSA2(AGND)_33") (pintype "power_in"))
      (node (ref "U1") (pin "43") (pinfunction "ADCLO_43") (pintype "input"))
      (node (ref "U1") (pin "44") (pinfunction "VSSAIO(AGND)_44") (pintype "power_in"))
      (node (ref "U1") (pin "58") (pinfunction "VSS2AGND_58") (pintype "power_in"))
    )
    (net (code "128") (name "GND") (class "Default")
      (node (ref "ADDRESS & CONTROL BUS") (pin "10") (pinfunction "10_10") (pintype "passive"))
      (node (ref "ADDRESS & CONTROL BUS") (pin "2") (pinfunction "2_2") (pintype "passive"))
      (node (ref "ADDRESS & CONTROL BUS") (pin "4") (pinfunction "4_4") (pintype "passive"))
      (node (ref "ADDRESS & CONTROL BUS") (pin "6") (pinfunction "6_6") (pintype "passive"))
      (node (ref "ADDRESS & CONTROL BUS") (pin "8") (pinfunction "8_8") (pintype "passive"))
      (node (ref "C1") (pin "1") (pinfunction "1_1") (pintype "passive"))
      (node (ref "C2") (pin "1") (pinfunction "1_1") (pintype "passive"))
      (node (ref "C3") (pin "1") (pinfunction "1_1") (pintype "passive"))
      (node (ref "DATA BUS") (pin "10") (pinfunction "10_10") (pintype "passive"))
      (node (ref "DATA BUS") (pin "12") (pinfunction "12_12") (pintype "passive"))
      (node (ref "DATA BUS") (pin "14") (pinfunction "14_14") (pintype "passive"))
      (node (ref "DATA BUS") (pin "16") (pinfunction "16_16") (pintype "passive"))
      (node (ref "DATA BUS") (pin "18") (pinfunction "18_18") (pintype "passive"))
      (node (ref "DATA BUS") (pin "2") (pinfunction "2_2") (pintype "passive"))
      (node (ref "DATA BUS") (pin "20") (pinfunction "20_20") (pintype "passive"))
      (node (ref "DATA BUS") (pin "22") (pinfunction "22_22") (pintype "passive"))
      (node (ref "DATA BUS") (pin "24") (pinfunction "24_24") (pintype "passive"))
      (node (ref "DATA BUS") (pin "26") (pinfunction "26_26") (pintype "passive"))
      (node (ref "DATA BUS") (pin "28") (pinfunction "28_28") (pintype "passive"))
      (node (ref "DATA BUS") (pin "30") (pinfunction "30_30") (pintype "passive"))
      (node (ref "DATA BUS") (pin "32") (pinfunction "32_32") (pintype "passive"))
      (node (ref "DATA BUS") (pin "4") (pinfunction "4_4") (pintype "passive"))
      (node (ref "DATA BUS") (pin "6") (pinfunction "6_6") (pintype "passive"))
      (node (ref "DATA BUS") (pin "8") (pinfunction "8_8") (pintype "passive"))
      (node (ref "LED1") (pin "2") (pinfunction "K_2") (pintype "passive"))
      (node (ref "OSC1") (pin "2") (pinfunction "GND_2") (pintype "power_in"))
      (node (ref "OSC2") (pin "4") (pinfunction "GND_4") (pintype "passive"))
      (node (ref "OSC2") (pin "7") (pinfunction "GND_7") (pintype "passive"))
      (node (ref "R1") (pin "1") (pinfunction "1_1") (pintype "passive"))
      (node (ref "R1") (pin "2") (pinfunction "2_2") (pintype "passive"))
      (node (ref "R1") (pin "3") (pinfunction "3_3") (pintype "passive"))
      (node (ref "R1") (pin "4") (pinfunction "4_4") (pintype "passive"))
      (node (ref "R15") (pin "2") (pinfunction "2_2") (pintype "passive"))
      (node (ref "U1") (pin "103") (pinfunction "VSS.10_103") (pintype "power_in"))
      (node (ref "U1") (pin "104") (pinfunction "X1_104") (pintype "input"))
      (node (ref "U1") (pin "106") (pinfunction "VSS.11_106") (pintype "power_in"))
      (node (ref "U1") (pin "108") (pinfunction "VSS.12_108") (pintype "power_in"))
      (node (ref "U1") (pin "118") (pinfunction "VSS.13_118") (pintype "power_in"))
      (node (ref "U1") (pin "120") (pinfunction "VSS.14_120") (pintype "power_in"))
      (node (ref "U1") (pin "125") (pinfunction "VSS.15_125") (pintype "power_in"))
      (node (ref "U1") (pin "14") (pinfunction "VSS.3_14") (pintype "power_in"))
      (node (ref "U1") (pin "140") (pinfunction "VSS.16_140") (pintype "power_in"))
      (node (ref "U1") (pin "144") (pinfunction "VSS.17_144") (pintype "power_in"))
      (node (ref "U1") (pin "147") (pinfunction "VSS.18_147") (pintype "power_in"))
      (node (ref "U1") (pin "155") (pinfunction "VSS.19_155") (pintype "power_in"))
      (node (ref "U1") (pin "160") (pinfunction "VSS.19_160") (pintype "power_in"))
      (node (ref "U1") (pin "166") (pinfunction "VSS.20_166") (pintype "power_in"))
      (node (ref "U1") (pin "171") (pinfunction "VSS.21_171") (pintype "power_in"))
      (node (ref "U1") (pin "22") (pinfunction "VSS.4_22") (pintype "power_in"))
      (node (ref "U1") (pin "3") (pinfunction "VSS.1_3") (pintype "power_in"))
      (node (ref "U1") (pin "30") (pinfunction "VSS.5_30") (pintype "power_in"))
      (node (ref "U1") (pin "60") (pinfunction "VSS.6_60") (pintype "power_in"))
      (node (ref "U1") (pin "70") (pinfunction "VSS.7_70") (pintype "power_in"))
      (node (ref "U1") (pin "8") (pinfunction "VSS.2_8") (pintype "power_in"))
      (node (ref "U1") (pin "83") (pinfunction "VSS.8_83") (pintype "power_in"))
      (node (ref "U1") (pin "92") (pinfunction "VSS.9_92") (pintype "power_in"))
    )
    (net (code "129") (name "Net-(DSP BOOT-Pad1)") (class "Default")
      (node (ref "DSP BOOT") (pin "1") (pinfunction "1_1") (pintype "passive"))
      (node (ref "R1") (pin "8") (pinfunction "8_8") (pintype "passive"))
    )
    (net (code "130") (name "Net-(DSP BOOT-Pad3)") (class "Default")
      (node (ref "DSP BOOT") (pin "3") (pinfunction "3_3") (pintype "passive"))
      (node (ref "R1") (pin "7") (pinfunction "7_7") (pintype "passive"))
    )
    (net (code "131") (name "Net-(DSP BOOT-Pad5)") (class "Default")
      (node (ref "DSP BOOT") (pin "5") (pinfunction "5_5") (pintype "passive"))
      (node (ref "R1") (pin "6") (pinfunction "6_6") (pintype "passive"))
    )
    (net (code "132") (name "Net-(DSP BOOT-Pad7)") (class "Default")
      (node (ref "DSP BOOT") (pin "7") (pinfunction "7_7") (pintype "passive"))
      (node (ref "R1") (pin "5") (pinfunction "5_5") (pintype "passive"))
    )
    (net (code "133") (name "Net-(LED1-A)") (class "Default")
      (node (ref "LED1") (pin "1") (pinfunction "A_1") (pintype "passive"))
      (node (ref "R22") (pin "2") (pinfunction "2_2") (pintype "passive"))
    )
    (net (code "134") (name "Net-(OSC1-OUT)") (class "Default")
      (node (ref "OSC1") (pin "3") (pinfunction "OUT_3") (pintype "output"))
      (node (ref "OSC2") (pin "11") (pinfunction "OUT_11") (pintype "passive"))
      (node (ref "OSC2") (pin "8") (pinfunction "OUT_8") (pintype "passive"))
      (node (ref "R11") (pin "1") (pinfunction "1_1") (pintype "passive"))
    )
    (net (code "135") (name "Net-(U1-XCLKOUT)") (class "Default")
      (node (ref "R10") (pin "1") (pinfunction "1_1") (pintype "passive"))
      (node (ref "U1") (pin "138") (pinfunction "XCLKOUT_138") (pintype "output"))
    )
    (net (code "136") (name "unconnected-(OSC2-EN-Pad1)") (class "Default")
      (node (ref "OSC2") (pin "1") (pinfunction "EN_1") (pintype "passive"))
    )
    (net (code "137") (name "unconnected-(OSC2-NC-Pad2)") (class "Default")
      (node (ref "OSC2") (pin "2") (pinfunction "NC_2") (pintype "passive"))
    )
    (net (code "138") (name "unconnected-(OSC2-NC-Pad3)") (class "Default")
      (node (ref "OSC2") (pin "3") (pinfunction "NC_3") (pintype "passive"))
    )
    (net (code "139") (name "unconnected-(OSC2-NC-Pad5)") (class "Default")
      (node (ref "OSC2") (pin "5") (pinfunction "NC_5") (pintype "passive"))
    )
    (net (code "140") (name "unconnected-(OSC2-NC-Pad6)") (class "Default")
      (node (ref "OSC2") (pin "6") (pinfunction "NC_6") (pintype "passive"))
    )
    (net (code "141") (name "unconnected-(OSC2-NC-Pad9)") (class "Default")
      (node (ref "OSC2") (pin "9") (pinfunction "NC_9") (pintype "passive"))
    )
    (net (code "142") (name "unconnected-(OSC2-NC-Pad10)") (class "Default")
      (node (ref "OSC2") (pin "10") (pinfunction "NC_10") (pintype "passive"))
    )
    (net (code "143") (name "unconnected-(OSC2-NC-Pad12)") (class "Default")
      (node (ref "OSC2") (pin "12") (pinfunction "NC_12") (pintype "passive"))
    )
    (net (code "144") (name "unconnected-(OSC2-NC-Pad13)") (class "Default")
      (node (ref "OSC2") (pin "13") (pinfunction "NC_13") (pintype "passive"))
    )
    (net (code "145") (name "unconnected-(U1-(NC)_TEST1-Pad81)") (class "Default")
      (node (ref "U1") (pin "81") (pinfunction "(NC)_TEST1_81") (pintype "input"))
    )
    (net (code "146") (name "unconnected-(U1-(NC)_TEST2-Pad82)") (class "Default")
      (node (ref "U1") (pin "82") (pinfunction "(NC)_TEST2_82") (pintype "input"))
    )
    (net (code "147") (name "unconnected-(U1-X2-Pad102)") (class "Default")
      (node (ref "U1") (pin "102") (pinfunction "X2_102") (pintype "input"))
    )
  )
)
